# Irdroid_USB_IRDA.net
KiCad netlist of a schematic drawn in EAGLE
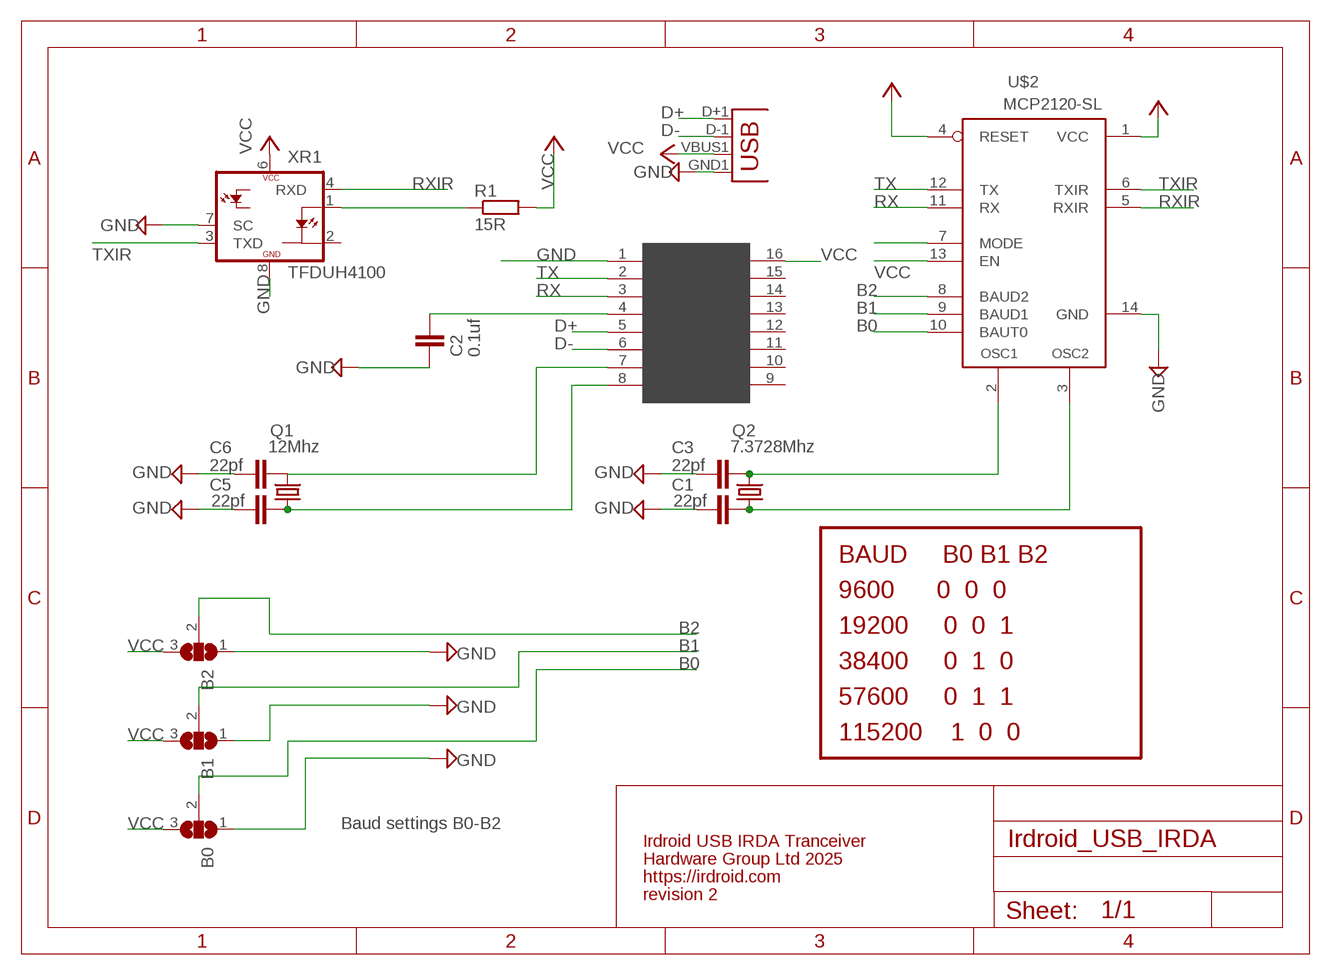
[diagram p0: schematic, sheet 1]

(export (version "E")
  (design (tool "Eeschema 10.0.6"))
  (components
    (comp (ref "B0")
      (value "SJ2W")
      (footprint "eagle-import:SJ_2")
      (libsource (lib "eagle-import") (part "SJ2W"))
    )
    (comp (ref "B1")
      (value "SJ2W")
      (footprint "eagle-import:SJ_2")
      (libsource (lib "eagle-import") (part "SJ2W"))
    )
    (comp (ref "B2")
      (value "SJ2W")
      (footprint "eagle-import:SJ_2")
      (libsource (lib "eagle-import") (part "SJ2W"))
    )
    (comp (ref "C1")
      (value "22pf")
      (footprint "eagle-import:C603")
      (libsource (lib "eagle-import") (part "CAPC603"))
    )
    (comp (ref "C2")
      (value "0.1uf")
      (footprint "eagle-import:C603")
      (libsource (lib "eagle-import") (part "CAPC603"))
    )
    (comp (ref "C3")
      (value "22pf")
      (footprint "eagle-import:C603")
      (libsource (lib "eagle-import") (part "CAPC603"))
    )
    (comp (ref "C5")
      (value "22pf")
      (footprint "eagle-import:C603")
      (libsource (lib "eagle-import") (part "CAPC603"))
    )
    (comp (ref "C6")
      (value "22pf")
      (footprint "eagle-import:C603")
      (libsource (lib "eagle-import") (part "CAPC603"))
    )
    (comp (ref "JP2")
      (value "USBA-SMD-MALE")
      (footprint "eagle-import:USB-A-SMT-MALE")
      (libsource (lib "eagle-import") (part "USBA-SMD-MALE"))
    )
    (comp (ref "Q1")
      (value "12Mhz")
      (footprint "eagle-import:HC49UP")
      (libsource (lib "eagle-import") (part "CRYSTALHC49UP"))
    )
    (comp (ref "Q2")
      (value "7.3728Mhz")
      (footprint "eagle-import:HC49UP")
      (libsource (lib "eagle-import") (part "CRYSTALHC49UP"))
    )
    (comp (ref "R1")
      (value "15R")
      (footprint "eagle-import:R0603")
      (libsource (lib "eagle-import") (part "R-EU_R0603"))
    )
    (comp (ref "U$1")
      (value "ch")
      (footprint "eagle-import:SOIC16")
      (libsource (lib "eagle-import") (part "CH340G"))
    )
    (comp (ref "U$2")
      (value "MCP2120-SL")
      (footprint "eagle-import:SO-14")
      (libsource (lib "eagle-import") (part "MCP2120-SL"))
    )
    (comp (ref "XR1")
      (value "TFDUH4100")
      (footprint "eagle-import:TFDU4-HOR")
      (fields (field (name "MPN") "TFDU4101-TT3"))
      (libsource (lib "eagle-import") (part "TFD?4100UH"))
    )
  )
  (nets
    (net (code "1") (name "/B0") (class "Default")
      (node (ref "B0") (pin "2") (pinfunction "2_2") (pintype "passive"))
      (node (ref "U$2") (pin "10") (pinfunction "BAUT0_10") (pintype "input"))
    )
    (net (code "2") (name "/B1") (class "Default")
      (node (ref "B1") (pin "2") (pinfunction "2_2") (pintype "passive"))
      (node (ref "U$2") (pin "9") (pinfunction "BAUD1_9") (pintype "input"))
    )
    (net (code "3") (name "/B2") (class "Default")
      (node (ref "B2") (pin "2") (pinfunction "2_2") (pintype "passive"))
      (node (ref "U$2") (pin "8") (pinfunction "BAUD2_8") (pintype "input"))
    )
    (net (code "4") (name "/D+") (class "Default")
      (node (ref "JP2") (pin "D+1") (pinfunction "D+_D+1") (pintype "bidirectional"))
      (node (ref "U$1") (pin "5") (pinfunction "D+_5") (pintype "bidirectional"))
    )
    (net (code "5") (name "/D-") (class "Default")
      (node (ref "JP2") (pin "D-1") (pinfunction "D-_D-1") (pintype "bidirectional"))
      (node (ref "U$1") (pin "6") (pinfunction "D-_6") (pintype "bidirectional"))
    )
    (net (code "6") (name "/RX") (class "Default")
      (node (ref "U$1") (pin "3") (pinfunction "RX_3") (pintype "bidirectional"))
      (node (ref "U$2") (pin "11") (pinfunction "RX_11") (pintype "output"))
    )
    (net (code "7") (name "/RXIR") (class "Default")
      (node (ref "U$2") (pin "5") (pinfunction "RXIR_5") (pintype "input"))
      (node (ref "XR1") (pin "4") (pinfunction "RXD_4") (pintype "output"))
    )
    (net (code "8") (name "/TX") (class "Default")
      (node (ref "U$1") (pin "2") (pinfunction "TX_2") (pintype "bidirectional"))
      (node (ref "U$2") (pin "12") (pinfunction "TX_12") (pintype "input"))
    )
    (net (code "9") (name "/TXIR") (class "Default")
      (node (ref "U$2") (pin "6") (pinfunction "TXIR_6") (pintype "output"))
      (node (ref "XR1") (pin "3") (pinfunction "TXD_3") (pintype "input"))
    )
    (net (code "10") (name "GND") (class "Default")
      (node (ref "B0") (pin "1") (pinfunction "1_1") (pintype "passive"))
      (node (ref "B1") (pin "1") (pinfunction "1_1") (pintype "passive"))
      (node (ref "B2") (pin "1") (pinfunction "1_1") (pintype "passive"))
      (node (ref "C1") (pin "2") (pinfunction "2_2") (pintype "passive"))
      (node (ref "C2") (pin "2") (pinfunction "2_2") (pintype "passive"))
      (node (ref "C3") (pin "2") (pinfunction "2_2") (pintype "passive"))
      (node (ref "C5") (pin "2") (pinfunction "2_2") (pintype "passive"))
      (node (ref "C6") (pin "2") (pinfunction "2_2") (pintype "passive"))
      (node (ref "JP2") (pin "GND1") (pinfunction "GND_GND1") (pintype "bidirectional"))
      (node (ref "U$1") (pin "1") (pinfunction "GND_1") (pintype "bidirectional"))
      (node (ref "U$2") (pin "14") (pinfunction "GND_14") (pintype "power_in"))
      (node (ref "XR1") (pin "7") (pinfunction "SC_7") (pintype "input"))
      (node (ref "XR1") (pin "8") (pinfunction "GND_8") (pintype "power_in"))
    )
    (net (code "11") (name "Net-(U$1-V3)") (class "Default")
      (node (ref "C2") (pin "1") (pinfunction "1_1") (pintype "passive"))
      (node (ref "U$1") (pin "4") (pinfunction "V3_4") (pintype "bidirectional"))
    )
    (net (code "12") (name "Net-(U$1-XI)") (class "Default")
      (node (ref "C6") (pin "1") (pinfunction "1_1") (pintype "passive"))
      (node (ref "Q1") (pin "2") (pinfunction "2_2") (pintype "passive"))
      (node (ref "U$1") (pin "7") (pinfunction "XI_7") (pintype "bidirectional"))
    )
    (net (code "13") (name "Net-(U$1-XO)") (class "Default")
      (node (ref "C5") (pin "1") (pinfunction "1_1") (pintype "passive"))
      (node (ref "Q1") (pin "1") (pinfunction "1_1") (pintype "passive"))
      (node (ref "U$1") (pin "8") (pinfunction "XO_8") (pintype "bidirectional"))
    )
    (net (code "14") (name "Net-(U$2-OSC1)") (class "Default")
      (node (ref "C3") (pin "1") (pinfunction "1_1") (pintype "passive"))
      (node (ref "Q2") (pin "2") (pinfunction "2_2") (pintype "passive"))
      (node (ref "U$2") (pin "2") (pinfunction "OSC1_2") (pintype "input"))
    )
    (net (code "15") (name "Net-(U$2-OSC2)") (class "Default")
      (node (ref "C1") (pin "1") (pinfunction "1_1") (pintype "passive"))
      (node (ref "Q2") (pin "1") (pinfunction "1_1") (pintype "passive"))
      (node (ref "U$2") (pin "3") (pinfunction "OSC2_3") (pintype "output"))
    )
    (net (code "16") (name "Net-(XR1-IRED-A)") (class "Default")
      (node (ref "R1") (pin "1") (pinfunction "1_1") (pintype "passive"))
      (node (ref "XR1") (pin "1") (pinfunction "IRED-A_1") (pintype "passive"))
    )
    (net (code "17") (name "VCC") (class "Default")
      (node (ref "B0") (pin "3") (pinfunction "3_3") (pintype "passive"))
      (node (ref "B1") (pin "3") (pinfunction "3_3") (pintype "passive"))
      (node (ref "B2") (pin "3") (pinfunction "3_3") (pintype "passive"))
      (node (ref "JP2") (pin "VBUS1") (pinfunction "VBUS_VBUS1") (pintype "bidirectional"))
      (node (ref "R1") (pin "2") (pinfunction "2_2") (pintype "passive"))
      (node (ref "U$1") (pin "16") (pinfunction "VCC_16") (pintype "bidirectional"))
      (node (ref "U$2") (pin "1") (pinfunction "VCC_1") (pintype "power_in"))
      (node (ref "U$2") (pin "13") (pinfunction "EN_13") (pintype "input"))
      (node (ref "U$2") (pin "4") (pinfunction "RESET_4") (pintype "bidirectional"))
      (node (ref "U$2") (pin "7") (pinfunction "MODE_7") (pintype "input"))
      (node (ref "XR1") (pin "6") (pinfunction "VCC_6") (pintype "power_in"))
    )
    (net (code "18") (name "unconnected-(U$1-CTS-Pad9)") (class "Default")
      (node (ref "U$1") (pin "9") (pinfunction "CTS_9") (pintype "bidirectional"))
    )
    (net (code "19") (name "unconnected-(U$1-DCD-Pad12)") (class "Default")
      (node (ref "U$1") (pin "12") (pinfunction "DCD_12") (pintype "bidirectional"))
    )
    (net (code "20") (name "unconnected-(U$1-DSR-Pad10)") (class "Default")
      (node (ref "U$1") (pin "10") (pinfunction "DSR_10") (pintype "bidirectional"))
    )
    (net (code "21") (name "unconnected-(U$1-DTR-Pad13)") (class "Default")
      (node (ref "U$1") (pin "13") (pinfunction "DTR_13") (pintype "bidirectional"))
    )
    (net (code "22") (name "unconnected-(U$1-RI-Pad11)") (class "Default")
      (node (ref "U$1") (pin "11") (pinfunction "RI_11") (pintype "bidirectional"))
    )
    (net (code "23") (name "unconnected-(U$1-RS232-Pad15)") (class "Default")
      (node (ref "U$1") (pin "15") (pinfunction "RS232_15") (pintype "bidirectional"))
    )
    (net (code "24") (name "unconnected-(U$1-RTS-Pad14)") (class "Default")
      (node (ref "U$1") (pin "14") (pinfunction "RTS_14") (pintype "bidirectional"))
    )
    (net (code "25") (name "unconnected-(XR1-IRED-C-Pad2)") (class "Default")
      (node (ref "XR1") (pin "2") (pinfunction "IRED-C_2") (pintype "output"))
    )
  )
)
